# sphere_robo.net
KiCad netlist of a schematic drawn in EAGLE
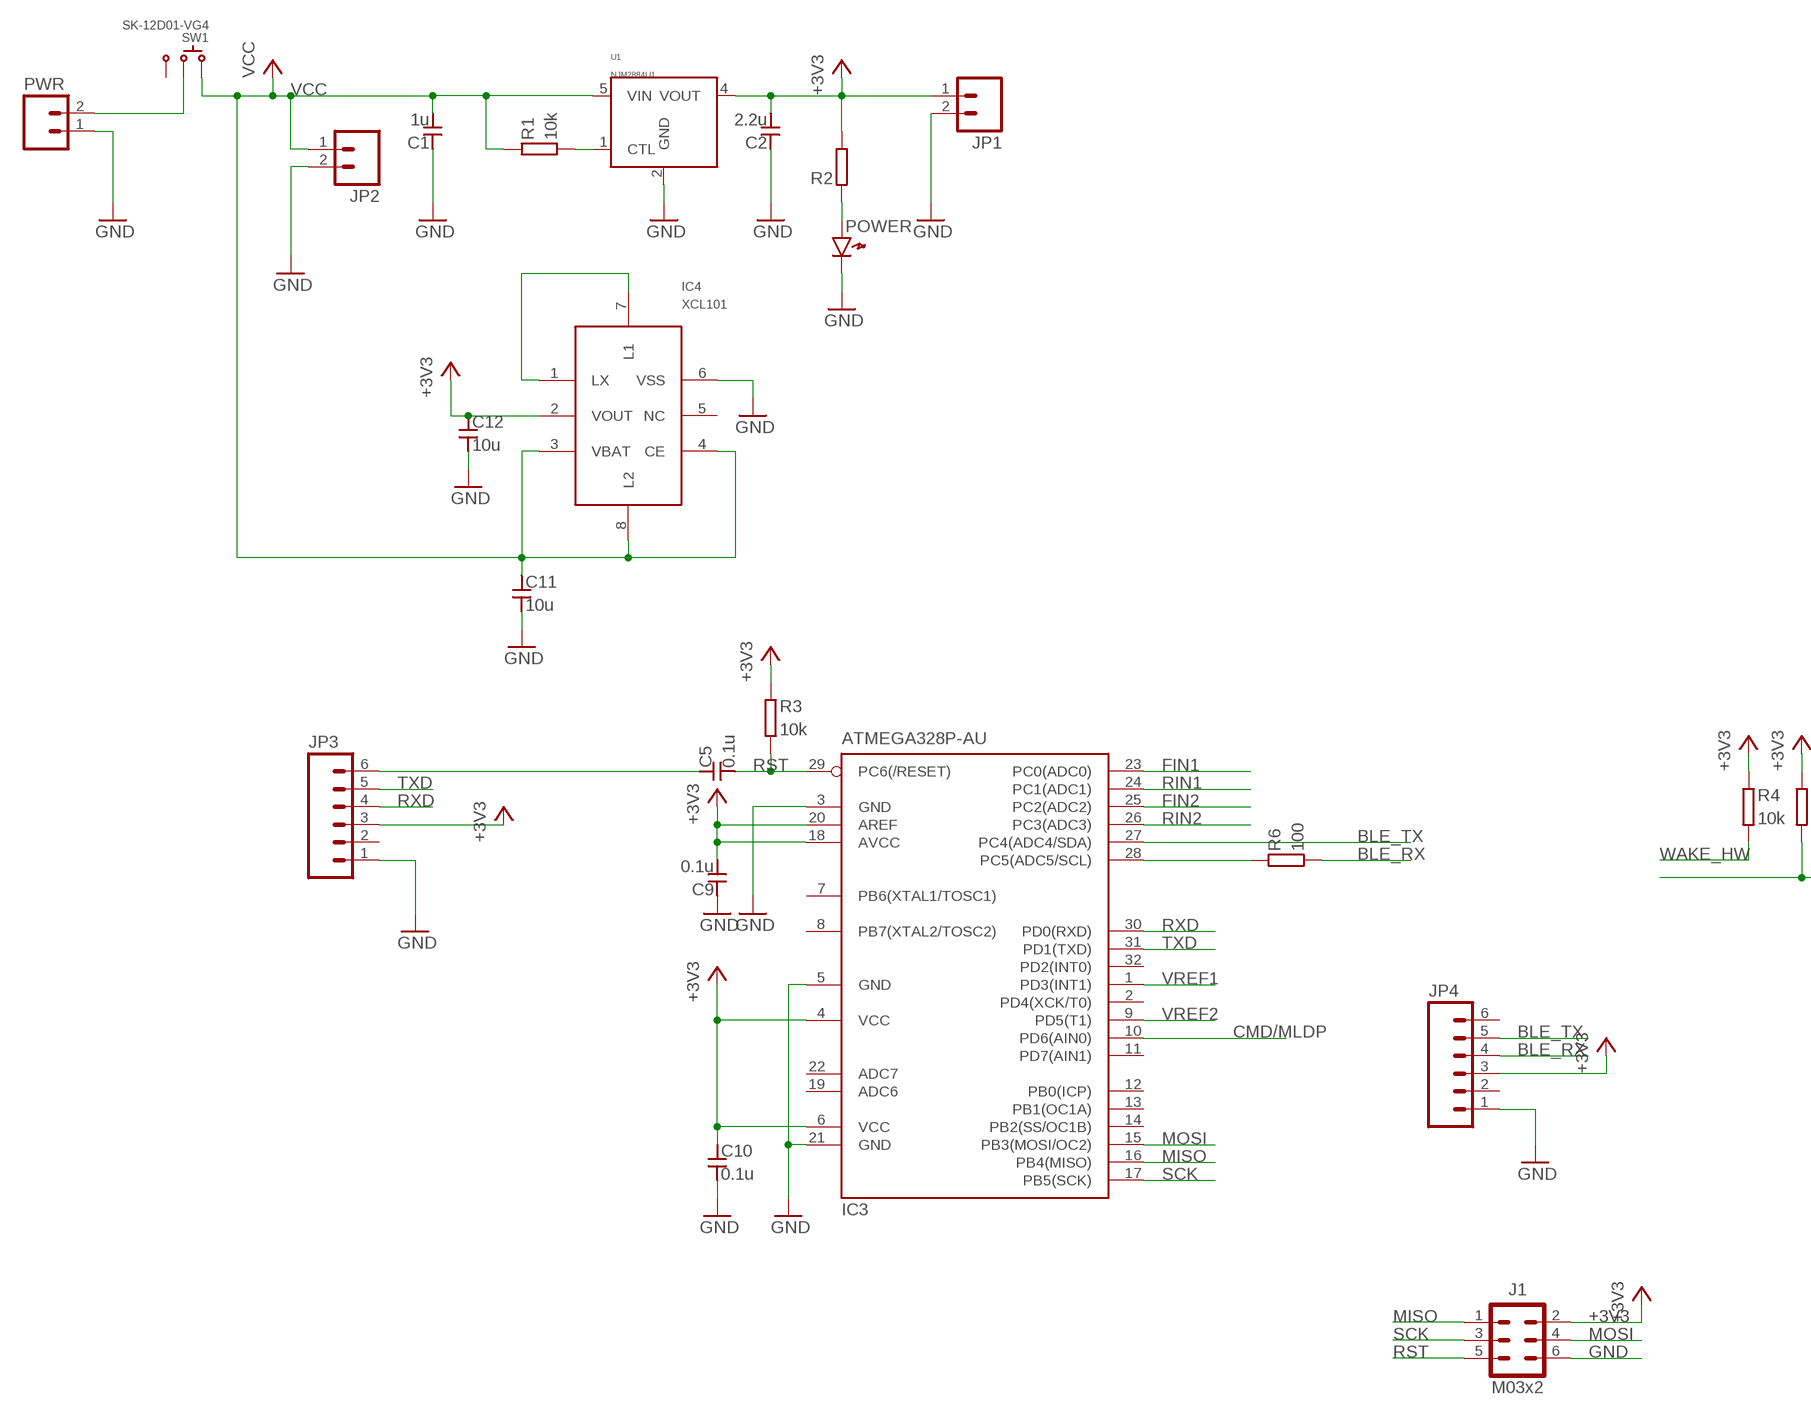
[diagram p0: schematic, sheet 1, part 1 of 2]
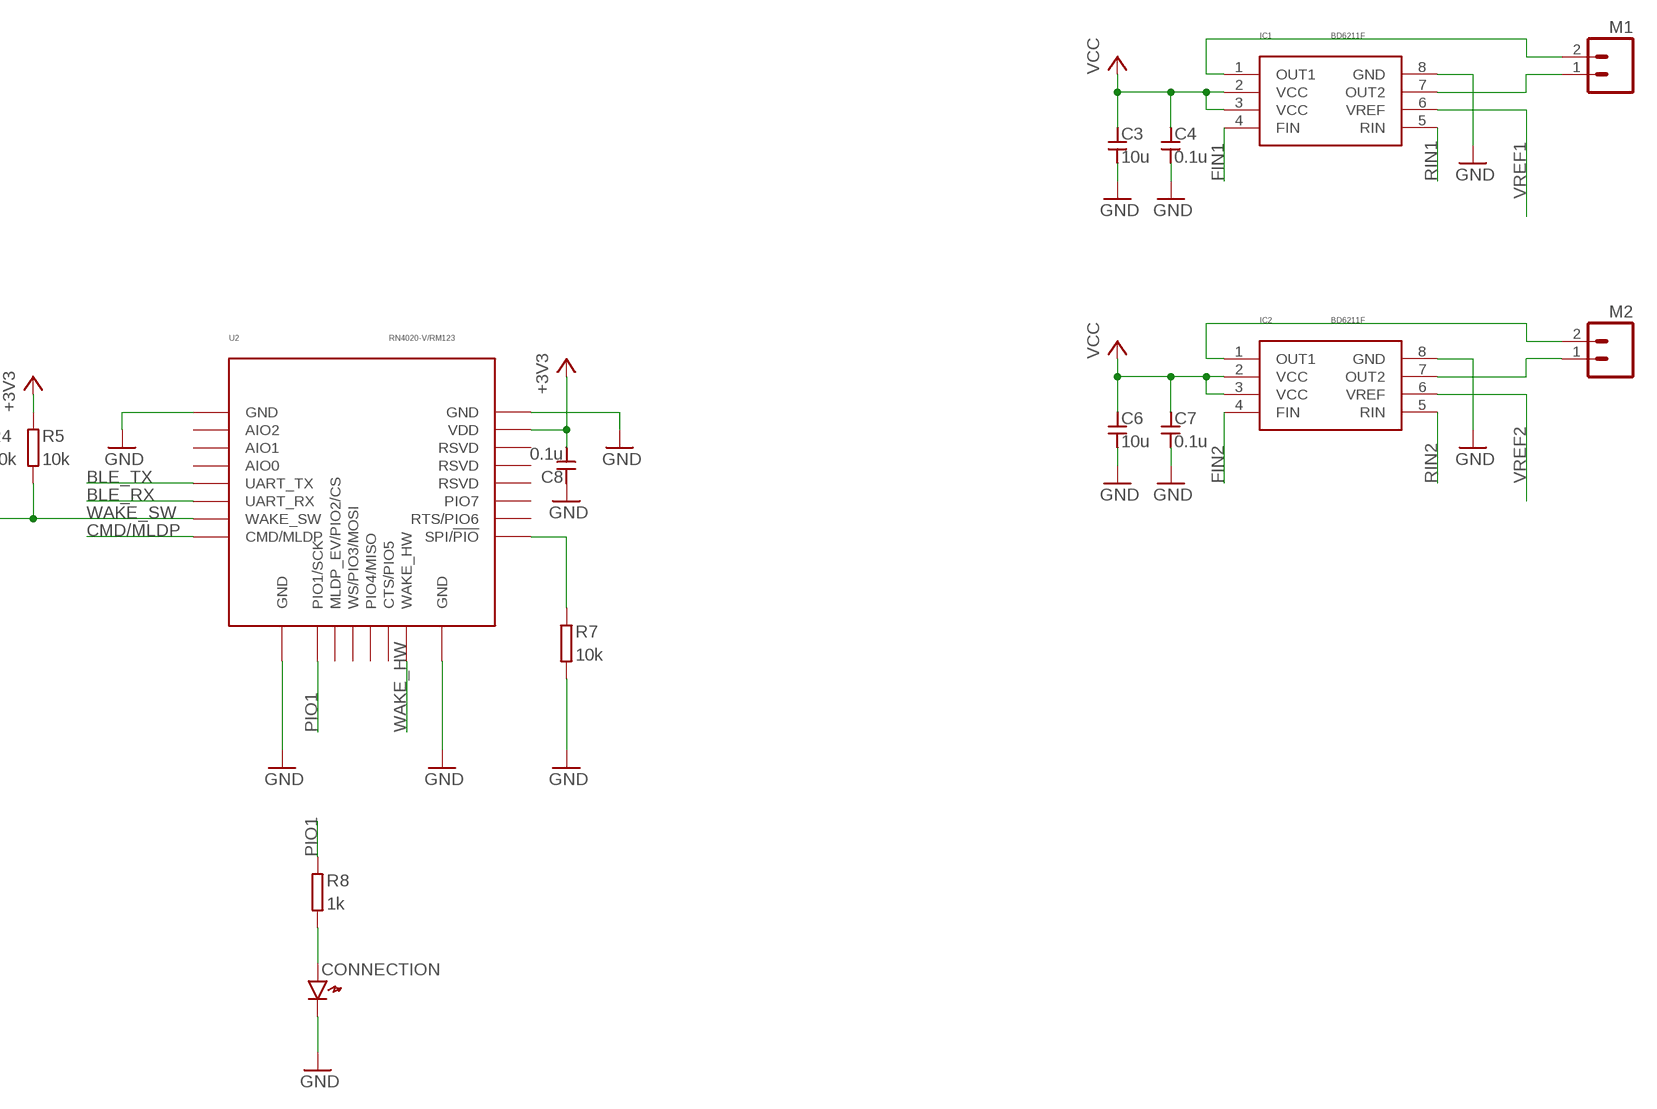
[diagram p1: schematic, sheet 1, part 2 of 2]

(export (version "E")
  (design (tool "Eeschema 10.0.6"))
  (components
    (comp (ref "C1")
      (value "1u")
      (footprint "eagle-import:SMD1608_REDUCED")
      (libsource (lib "eagle-import") (part "CAPACITOR1608_REDUCED"))
    )
    (comp (ref "C2")
      (value "2.2u")
      (footprint "eagle-import:SMD1608_REDUCED")
      (libsource (lib "eagle-import") (part "CAPACITOR1608_REDUCED"))
    )
    (comp (ref "C3")
      (value "10u")
      (footprint "eagle-import:SMD2012_REDUCED")
      (libsource (lib "eagle-import") (part "CAPACITOR2012_REDUCED"))
    )
    (comp (ref "C4")
      (value "0.1u")
      (footprint "eagle-import:SMD1608_REDUCED")
      (libsource (lib "eagle-import") (part "CAPACITOR1608_REDUCED"))
    )
    (comp (ref "C5")
      (value "0.1u")
      (footprint "eagle-import:SMD1608_REDUCED")
      (libsource (lib "eagle-import") (part "CAPACITOR1608_REDUCED"))
    )
    (comp (ref "C6")
      (value "10u")
      (footprint "eagle-import:SMD2012_REDUCED")
      (libsource (lib "eagle-import") (part "CAPACITOR2012_REDUCED"))
    )
    (comp (ref "C7")
      (value "0.1u")
      (footprint "eagle-import:SMD1608_REDUCED")
      (libsource (lib "eagle-import") (part "CAPACITOR1608_REDUCED"))
    )
    (comp (ref "C8")
      (value "0.1u")
      (footprint "eagle-import:SMD1608_REDUCED")
      (libsource (lib "eagle-import") (part "CAPACITOR1608_REDUCED"))
    )
    (comp (ref "C9")
      (value "0.1u")
      (footprint "eagle-import:SMD1608_REDUCED")
      (libsource (lib "eagle-import") (part "CAPACITOR1608_REDUCED"))
    )
    (comp (ref "C10")
      (value "0.1u")
      (footprint "eagle-import:SMD1608_REDUCED")
      (libsource (lib "eagle-import") (part "CAPACITOR1608_REDUCED"))
    )
    (comp (ref "C11")
      (value "10u")
      (footprint "eagle-import:SMD2012_REDUCED")
      (libsource (lib "eagle-import") (part "CAPACITOR2012_REDUCED"))
    )
    (comp (ref "C12")
      (value "10u")
      (footprint "eagle-import:SMD2012_REDUCED")
      (libsource (lib "eagle-import") (part "CAPACITOR2012_REDUCED"))
    )
    (comp (ref "CONNECTION")
      (value "LED1608_REDUCED")
      (footprint "eagle-import:LED1608_REDUCED")
      (libsource (lib "eagle-import") (part "LED1608_REDUCED"))
    )
    (comp (ref "IC1")
      (value "BD6211F")
      (footprint "eagle-import:SOP-8")
      (libsource (lib "eagle-import") (part "BD6211F"))
    )
    (comp (ref "IC2")
      (value "BD6211F")
      (footprint "eagle-import:SOP-8")
      (libsource (lib "eagle-import") (part "BD6211F"))
    )
    (comp (ref "IC3")
      (value "ATMEGA328P-AU")
      (footprint "eagle-import:TQFP32-08")
      (libsource (lib "eagle-import") (part "ATMEGA328P-AU"))
    )
    (comp (ref "IC4")
      (value "XCL101")
      (footprint "eagle-import:CL-2025")
      (libsource (lib "eagle-import") (part "XCL101"))
    )
    (comp (ref "J1")
      (value "M03X2STD")
      (footprint "eagle-import:2X03")
      (libsource (lib "eagle-import") (part "M03X2STD"))
    )
    (comp (ref "JP1")
      (value "M02NOSILK")
      (footprint "eagle-import:1X02-NOSILK")
      (libsource (lib "eagle-import") (part "M02NOSILK"))
    )
    (comp (ref "JP2")
      (value "M02NOSILK")
      (footprint "eagle-import:1X02-NOSILK")
      (libsource (lib "eagle-import") (part "M02NOSILK"))
    )
    (comp (ref "JP3")
      (value "M06NOSILK")
      (footprint "eagle-import:1X06-NOSILK")
      (libsource (lib "eagle-import") (part "M06NOSILK"))
    )
    (comp (ref "JP4")
      (value "M06NOSILK")
      (footprint "eagle-import:1X06-NOSILK")
      (libsource (lib "eagle-import") (part "M06NOSILK"))
    )
    (comp (ref "M1")
      (value "M02NOSILK")
      (footprint "eagle-import:1X02-NOSILK")
      (libsource (lib "eagle-import") (part "M02NOSILK"))
    )
    (comp (ref "M2")
      (value "M02NOSILK")
      (footprint "eagle-import:1X02-NOSILK")
      (libsource (lib "eagle-import") (part "M02NOSILK"))
    )
    (comp (ref "POWER")
      (value "LED1608_REDUCED")
      (footprint "eagle-import:LED1608_REDUCED")
      (libsource (lib "eagle-import") (part "LED1608_REDUCED"))
    )
    (comp (ref "PWR")
      (value "M02NOSILK")
      (footprint "eagle-import:1X02-NOSILK")
      (libsource (lib "eagle-import") (part "M02NOSILK"))
    )
    (comp (ref "R1")
      (value "10k")
      (footprint "eagle-import:SMD1608_REDUCED")
      (libsource (lib "eagle-import") (part "RESISTOR1608_REDUCED"))
    )
    (comp (ref "R2")
      (value "RESISTOR1608_REDUCED")
      (footprint "eagle-import:SMD1608_REDUCED")
      (libsource (lib "eagle-import") (part "RESISTOR1608_REDUCED"))
    )
    (comp (ref "R3")
      (value "10k")
      (footprint "eagle-import:SMD1608_REDUCED")
      (libsource (lib "eagle-import") (part "RESISTOR1608_REDUCED"))
    )
    (comp (ref "R4")
      (value "10k")
      (footprint "eagle-import:SMD1608_REDUCED")
      (libsource (lib "eagle-import") (part "RESISTOR1608_REDUCED"))
    )
    (comp (ref "R5")
      (value "10k")
      (footprint "eagle-import:SMD1608_REDUCED")
      (libsource (lib "eagle-import") (part "RESISTOR1608_REDUCED"))
    )
    (comp (ref "R6")
      (value "100")
      (footprint "eagle-import:SMD1608_REDUCED")
      (libsource (lib "eagle-import") (part "RESISTOR1608_REDUCED"))
    )
    (comp (ref "R7")
      (value "10k")
      (footprint "eagle-import:SMD1608_REDUCED")
      (libsource (lib "eagle-import") (part "RESISTOR1608_REDUCED"))
    )
    (comp (ref "R8")
      (value "1k")
      (footprint "eagle-import:SMD1608_REDUCED")
      (libsource (lib "eagle-import") (part "RESISTOR1608_REDUCED"))
    )
    (comp (ref "SW1")
      (value "SK-12D01-VG4")
      (footprint "eagle-import:SK-12D01-VG4")
      (libsource (lib "eagle-import") (part "SK-12D01-VG4"))
    )
    (comp (ref "U1")
      (value "NJM2884U1")
      (footprint "eagle-import:SOT-89-5")
      (libsource (lib "eagle-import") (part "NJM2884U1"))
    )
    (comp (ref "U2")
      (value "RN4020-V/RM123")
      (footprint "eagle-import:RN4020")
      (libsource (lib "eagle-import") (part "RN4020-V/RM123"))
    )
  )
  (nets
    (net (code "1") (name "+3V3") (class "Default")
      (node (ref "C10") (pin "1") (pinfunction "1_1") (pintype "passive"))
      (node (ref "C12") (pin "1") (pinfunction "1_1") (pintype "passive"))
      (node (ref "C2") (pin "2") (pinfunction "2_2") (pintype "passive"))
      (node (ref "C8") (pin "2") (pinfunction "2_2") (pintype "passive"))
      (node (ref "C9") (pin "2") (pinfunction "2_2") (pintype "passive"))
      (node (ref "IC3") (pin "18") (pinfunction "AVCC_18") (pintype "power_in"))
      (node (ref "IC3") (pin "20") (pinfunction "AREF_20") (pintype "passive"))
      (node (ref "IC3") (pin "4") (pinfunction "VCC_4") (pintype "power_in"))
      (node (ref "IC3") (pin "6") (pinfunction "VCC_6") (pintype "power_in"))
      (node (ref "IC4") (pin "2") (pinfunction "VOUT_2") (pintype "bidirectional"))
      (node (ref "J1") (pin "2") (pinfunction "2_2") (pintype "bidirectional"))
      (node (ref "JP1") (pin "1") (pinfunction "1_1") (pintype "passive"))
      (node (ref "JP3") (pin "3") (pinfunction "3_3") (pintype "passive"))
      (node (ref "JP4") (pin "3") (pinfunction "3_3") (pintype "passive"))
      (node (ref "R2") (pin "2") (pinfunction "2_2") (pintype "passive"))
      (node (ref "R3") (pin "1") (pinfunction "1_1") (pintype "passive"))
      (node (ref "R4") (pin "1") (pinfunction "1_1") (pintype "passive"))
      (node (ref "R5") (pin "1") (pinfunction "1_1") (pintype "passive"))
      (node (ref "U1") (pin "4") (pinfunction "VOUT_4") (pintype "bidirectional"))
      (node (ref "U2") (pin "23") (pinfunction "VDD_23") (pintype "bidirectional"))
    )
    (net (code "2") (name "/BLE_RX") (class "Default")
      (node (ref "JP4") (pin "4") (pinfunction "4_4") (pintype "passive"))
      (node (ref "R6") (pin "2") (pinfunction "2_2") (pintype "passive"))
      (node (ref "U2") (pin "6") (pinfunction "UART_RX_6") (pintype "bidirectional"))
    )
    (net (code "3") (name "/BLE_TX") (class "Default")
      (node (ref "IC3") (pin "27") (pinfunction "PC4(ADC4/SDA)_27") (pintype "bidirectional"))
      (node (ref "JP4") (pin "5") (pinfunction "5_5") (pintype "passive"))
      (node (ref "U2") (pin "5") (pinfunction "UART_TX_5") (pintype "bidirectional"))
    )
    (net (code "4") (name "/CMD{slash}MLDP") (class "Default")
      (node (ref "IC3") (pin "10") (pinfunction "PD6(AIN0)_10") (pintype "bidirectional"))
      (node (ref "U2") (pin "8") (pinfunction "CMD/MLDP_8") (pintype "bidirectional"))
    )
    (net (code "5") (name "/FIN1") (class "Default")
      (node (ref "IC1") (pin "4") (pinfunction "FIN_4") (pintype "bidirectional"))
      (node (ref "IC3") (pin "23") (pinfunction "PC0(ADC0)_23") (pintype "bidirectional"))
    )
    (net (code "6") (name "/FIN2") (class "Default")
      (node (ref "IC2") (pin "4") (pinfunction "FIN_4") (pintype "bidirectional"))
      (node (ref "IC3") (pin "25") (pinfunction "PC2(ADC2)_25") (pintype "bidirectional"))
    )
    (net (code "7") (name "/MISO") (class "Default")
      (node (ref "IC3") (pin "16") (pinfunction "PB4(MISO)_16") (pintype "bidirectional"))
      (node (ref "J1") (pin "1") (pinfunction "1_1") (pintype "bidirectional"))
    )
    (net (code "8") (name "/MOSI") (class "Default")
      (node (ref "IC3") (pin "15") (pinfunction "PB3(MOSI/OC2)_15") (pintype "bidirectional"))
      (node (ref "J1") (pin "4") (pinfunction "4_4") (pintype "bidirectional"))
    )
    (net (code "9") (name "/PIO1") (class "Default")
      (node (ref "R8") (pin "1") (pinfunction "1_1") (pintype "passive"))
      (node (ref "U2") (pin "10") (pinfunction "PIO1/SCK_10") (pintype "bidirectional"))
    )
    (net (code "10") (name "/RIN1") (class "Default")
      (node (ref "IC1") (pin "5") (pinfunction "RIN_5") (pintype "bidirectional"))
      (node (ref "IC3") (pin "24") (pinfunction "PC1(ADC1)_24") (pintype "bidirectional"))
    )
    (net (code "11") (name "/RIN2") (class "Default")
      (node (ref "IC2") (pin "5") (pinfunction "RIN_5") (pintype "bidirectional"))
      (node (ref "IC3") (pin "26") (pinfunction "PC3(ADC3)_26") (pintype "bidirectional"))
    )
    (net (code "12") (name "/RST") (class "Default")
      (node (ref "C5") (pin "2") (pinfunction "2_2") (pintype "passive"))
      (node (ref "IC3") (pin "29") (pinfunction "PC6(/RESET)_29") (pintype "bidirectional"))
      (node (ref "J1") (pin "5") (pinfunction "5_5") (pintype "bidirectional"))
      (node (ref "R3") (pin "2") (pinfunction "2_2") (pintype "passive"))
    )
    (net (code "13") (name "/RXD") (class "Default")
      (node (ref "IC3") (pin "30") (pinfunction "PD0(RXD)_30") (pintype "bidirectional"))
      (node (ref "JP3") (pin "4") (pinfunction "4_4") (pintype "passive"))
    )
    (net (code "14") (name "/SCK") (class "Default")
      (node (ref "IC3") (pin "17") (pinfunction "PB5(SCK)_17") (pintype "bidirectional"))
      (node (ref "J1") (pin "3") (pinfunction "3_3") (pintype "bidirectional"))
    )
    (net (code "15") (name "/TXD") (class "Default")
      (node (ref "IC3") (pin "31") (pinfunction "PD1(TXD)_31") (pintype "bidirectional"))
      (node (ref "JP3") (pin "5") (pinfunction "5_5") (pintype "passive"))
    )
    (net (code "16") (name "/VREF1") (class "Default")
      (node (ref "IC1") (pin "6") (pinfunction "VREF_6") (pintype "bidirectional"))
      (node (ref "IC3") (pin "1") (pinfunction "PD3(INT1)_1") (pintype "bidirectional"))
    )
    (net (code "17") (name "/VREF2") (class "Default")
      (node (ref "IC2") (pin "6") (pinfunction "VREF_6") (pintype "bidirectional"))
      (node (ref "IC3") (pin "9") (pinfunction "PD5(T1)_9") (pintype "bidirectional"))
    )
    (net (code "18") (name "/WAKE_HW") (class "Default")
      (node (ref "R4") (pin "2") (pinfunction "2_2") (pintype "passive"))
      (node (ref "U2") (pin "15") (pinfunction "WAKE_HW_15") (pintype "bidirectional"))
    )
    (net (code "19") (name "/WAKE_SW") (class "Default")
      (node (ref "R5") (pin "2") (pinfunction "2_2") (pintype "passive"))
      (node (ref "U2") (pin "7") (pinfunction "WAKE_SW_7") (pintype "bidirectional"))
    )
    (net (code "20") (name "GND") (class "Default")
      (node (ref "C1") (pin "1") (pinfunction "1_1") (pintype "passive"))
      (node (ref "C10") (pin "2") (pinfunction "2_2") (pintype "passive"))
      (node (ref "C11") (pin "2") (pinfunction "2_2") (pintype "passive"))
      (node (ref "C12") (pin "2") (pinfunction "2_2") (pintype "passive"))
      (node (ref "C2") (pin "1") (pinfunction "1_1") (pintype "passive"))
      (node (ref "C3") (pin "2") (pinfunction "2_2") (pintype "passive"))
      (node (ref "C4") (pin "2") (pinfunction "2_2") (pintype "passive"))
      (node (ref "C6") (pin "2") (pinfunction "2_2") (pintype "passive"))
      (node (ref "C7") (pin "2") (pinfunction "2_2") (pintype "passive"))
      (node (ref "C8") (pin "1") (pinfunction "1_1") (pintype "passive"))
      (node (ref "C9") (pin "1") (pinfunction "1_1") (pintype "passive"))
      (node (ref "CONNECTION") (pin "K") (pinfunction "K_K") (pintype "passive"))
      (node (ref "IC1") (pin "8") (pinfunction "GND_8") (pintype "bidirectional"))
      (node (ref "IC2") (pin "8") (pinfunction "GND_8") (pintype "bidirectional"))
      (node (ref "IC3") (pin "21") (pinfunction "GND_21") (pintype "power_in"))
      (node (ref "IC3") (pin "3") (pinfunction "GND_3") (pintype "power_in"))
      (node (ref "IC3") (pin "5") (pinfunction "GND_5") (pintype "power_in"))
      (node (ref "IC4") (pin "6") (pinfunction "VSS_6") (pintype "bidirectional"))
      (node (ref "J1") (pin "6") (pinfunction "6_6") (pintype "bidirectional"))
      (node (ref "JP1") (pin "2") (pinfunction "2_2") (pintype "passive"))
      (node (ref "JP2") (pin "2") (pinfunction "2_2") (pintype "passive"))
      (node (ref "JP3") (pin "1") (pinfunction "1_1") (pintype "passive"))
      (node (ref "JP4") (pin "1") (pinfunction "1_1") (pintype "passive"))
      (node (ref "POWER") (pin "K") (pinfunction "K_K") (pintype "passive"))
      (node (ref "PWR") (pin "1") (pinfunction "1_1") (pintype "passive"))
      (node (ref "R7") (pin "2") (pinfunction "2_2") (pintype "passive"))
      (node (ref "U1") (pin "2") (pinfunction "GND_2") (pintype "bidirectional"))
      (node (ref "U2") (pin "1") (pinfunction "GND_1") (pintype "bidirectional"))
      (node (ref "U2") (pin "16") (pinfunction "GND_16") (pintype "bidirectional"))
      (node (ref "U2") (pin "24") (pinfunction "GND_24") (pintype "bidirectional"))
      (node (ref "U2") (pin "9") (pinfunction "GND_9") (pintype "bidirectional"))
    )
    (net (code "21") (name "Net-(C5-Pad1)") (class "Default")
      (node (ref "C5") (pin "1") (pinfunction "1_1") (pintype "passive"))
      (node (ref "JP3") (pin "6") (pinfunction "6_6") (pintype "passive"))
    )
    (net (code "22") (name "Net-(CONNECTION-PadA)") (class "Default")
      (node (ref "CONNECTION") (pin "A") (pinfunction "A_A") (pintype "passive"))
      (node (ref "R8") (pin "2") (pinfunction "2_2") (pintype "passive"))
    )
    (net (code "23") (name "Net-(IC1-OUT1)") (class "Default")
      (node (ref "IC1") (pin "1") (pinfunction "OUT1_1") (pintype "bidirectional"))
      (node (ref "M1") (pin "2") (pinfunction "2_2") (pintype "passive"))
    )
    (net (code "24") (name "Net-(IC1-OUT2)") (class "Default")
      (node (ref "IC1") (pin "7") (pinfunction "OUT2_7") (pintype "bidirectional"))
      (node (ref "M1") (pin "1") (pinfunction "1_1") (pintype "passive"))
    )
    (net (code "25") (name "Net-(IC2-OUT1)") (class "Default")
      (node (ref "IC2") (pin "1") (pinfunction "OUT1_1") (pintype "bidirectional"))
      (node (ref "M2") (pin "2") (pinfunction "2_2") (pintype "passive"))
    )
    (net (code "26") (name "Net-(IC2-OUT2)") (class "Default")
      (node (ref "IC2") (pin "7") (pinfunction "OUT2_7") (pintype "bidirectional"))
      (node (ref "M2") (pin "1") (pinfunction "1_1") (pintype "passive"))
    )
    (net (code "27") (name "Net-(IC3-PC5(ADC5{slash}SCL))") (class "Default")
      (node (ref "IC3") (pin "28") (pinfunction "PC5(ADC5/SCL)_28") (pintype "bidirectional"))
      (node (ref "R6") (pin "1") (pinfunction "1_1") (pintype "passive"))
    )
    (net (code "28") (name "Net-(IC4-L1)") (class "Default")
      (node (ref "IC4") (pin "1") (pinfunction "LX_1") (pintype "bidirectional"))
      (node (ref "IC4") (pin "7") (pinfunction "L1_7") (pintype "bidirectional"))
    )
    (net (code "29") (name "Net-(POWER-PadA)") (class "Default")
      (node (ref "POWER") (pin "A") (pinfunction "A_A") (pintype "passive"))
      (node (ref "R2") (pin "1") (pinfunction "1_1") (pintype "passive"))
    )
    (net (code "30") (name "Net-(SW1-P$2)") (class "Default")
      (node (ref "PWR") (pin "2") (pinfunction "2_2") (pintype "passive"))
      (node (ref "SW1") (pin "2") (pinfunction "P$2_2") (pintype "bidirectional"))
    )
    (net (code "31") (name "Net-(U1-CTL)") (class "Default")
      (node (ref "R1") (pin "2") (pinfunction "2_2") (pintype "passive"))
      (node (ref "U1") (pin "1") (pinfunction "CTL_1") (pintype "bidirectional"))
    )
    (net (code "32") (name "Net-(U2-SPI{slash}~{PIO})") (class "Default")
      (node (ref "R7") (pin "1") (pinfunction "1_1") (pintype "passive"))
      (node (ref "U2") (pin "17") (pinfunction "SPI/~{PIO}_17") (pintype "bidirectional"))
    )
    (net (code "33") (name "VCC") (class "Default")
      (node (ref "C1") (pin "2") (pinfunction "2_2") (pintype "passive"))
      (node (ref "C11") (pin "1") (pinfunction "1_1") (pintype "passive"))
      (node (ref "C3") (pin "1") (pinfunction "1_1") (pintype "passive"))
      (node (ref "C4") (pin "1") (pinfunction "1_1") (pintype "passive"))
      (node (ref "C6") (pin "1") (pinfunction "1_1") (pintype "passive"))
      (node (ref "C7") (pin "1") (pinfunction "1_1") (pintype "passive"))
      (node (ref "IC1") (pin "2") (pinfunction "VCC_2") (pintype "bidirectional"))
      (node (ref "IC1") (pin "3") (pinfunction "VCC_3") (pintype "bidirectional"))
      (node (ref "IC2") (pin "2") (pinfunction "VCC_2") (pintype "bidirectional"))
      (node (ref "IC2") (pin "3") (pinfunction "VCC_3") (pintype "bidirectional"))
      (node (ref "IC4") (pin "3") (pinfunction "VBAT_3") (pintype "bidirectional"))
      (node (ref "IC4") (pin "4") (pinfunction "CE_4") (pintype "bidirectional"))
      (node (ref "IC4") (pin "8") (pinfunction "L2_8") (pintype "bidirectional"))
      (node (ref "JP2") (pin "1") (pinfunction "1_1") (pintype "passive"))
      (node (ref "R1") (pin "1") (pinfunction "1_1") (pintype "passive"))
      (node (ref "SW1") (pin "1") (pinfunction "P$1_1") (pintype "bidirectional"))
      (node (ref "U1") (pin "5") (pinfunction "VIN_5") (pintype "bidirectional"))
    )
    (net (code "34") (name "unconnected-(IC3-ADC6-Pad19)") (class "Default")
      (node (ref "IC3") (pin "19") (pinfunction "ADC6_19") (pintype "input"))
    )
    (net (code "35") (name "unconnected-(IC3-ADC7-Pad22)") (class "Default")
      (node (ref "IC3") (pin "22") (pinfunction "ADC7_22") (pintype "input"))
    )
    (net (code "36") (name "unconnected-(IC3-PB0(ICP)-Pad12)") (class "Default")
      (node (ref "IC3") (pin "12") (pinfunction "PB0(ICP)_12") (pintype "bidirectional"))
    )
    (net (code "37") (name "unconnected-(IC3-PB1(OC1A)-Pad13)") (class "Default")
      (node (ref "IC3") (pin "13") (pinfunction "PB1(OC1A)_13") (pintype "bidirectional"))
    )
    (net (code "38") (name "unconnected-(IC3-PB2(SS{slash}OC1B)-Pad14)") (class "Default")
      (node (ref "IC3") (pin "14") (pinfunction "PB2(SS/OC1B)_14") (pintype "bidirectional"))
    )
    (net (code "39") (name "unconnected-(IC3-PB6(XTAL1{slash}TOSC1)-Pad7)") (class "Default")
      (node (ref "IC3") (pin "7") (pinfunction "PB6(XTAL1/TOSC1)_7") (pintype "bidirectional"))
    )
    (net (code "40") (name "unconnected-(IC3-PB7(XTAL2{slash}TOSC2)-Pad8)") (class "Default")
      (node (ref "IC3") (pin "8") (pinfunction "PB7(XTAL2/TOSC2)_8") (pintype "bidirectional"))
    )
    (net (code "41") (name "unconnected-(IC3-PD2(INT0)-Pad32)") (class "Default")
      (node (ref "IC3") (pin "32") (pinfunction "PD2(INT0)_32") (pintype "bidirectional"))
    )
    (net (code "42") (name "unconnected-(IC3-PD4(XCK{slash}T0)-Pad2)") (class "Default")
      (node (ref "IC3") (pin "2") (pinfunction "PD4(XCK/T0)_2") (pintype "bidirectional"))
    )
    (net (code "43") (name "unconnected-(IC3-PD7(AIN1)-Pad11)") (class "Default")
      (node (ref "IC3") (pin "11") (pinfunction "PD7(AIN1)_11") (pintype "bidirectional"))
    )
    (net (code "44") (name "unconnected-(IC4-NC-Pad5)") (class "Default")
      (node (ref "IC4") (pin "5") (pinfunction "NC_5") (pintype "bidirectional"))
    )
    (net (code "45") (name "unconnected-(JP3-Pad2)") (class "Default")
      (node (ref "JP3") (pin "2") (pinfunction "2_2") (pintype "passive"))
    )
    (net (code "46") (name "unconnected-(JP4-Pad2)") (class "Default")
      (node (ref "JP4") (pin "2") (pinfunction "2_2") (pintype "passive"))
    )
    (net (code "47") (name "unconnected-(JP4-Pad6)") (class "Default")
      (node (ref "JP4") (pin "6") (pinfunction "6_6") (pintype "passive"))
    )
    (net (code "48") (name "unconnected-(SW1-P$3-Pad3)") (class "Default")
      (node (ref "SW1") (pin "3") (pinfunction "P$3_3") (pintype "bidirectional"))
    )
    (net (code "49") (name "unconnected-(U2-AIO0-Pad4)") (class "Default")
      (node (ref "U2") (pin "4") (pinfunction "AIO0_4") (pintype "bidirectional"))
    )
    (net (code "50") (name "unconnected-(U2-AIO1-Pad3)") (class "Default")
      (node (ref "U2") (pin "3") (pinfunction "AIO1_3") (pintype "bidirectional"))
    )
    (net (code "51") (name "unconnected-(U2-AIO2-Pad2)") (class "Default")
      (node (ref "U2") (pin "2") (pinfunction "AIO2_2") (pintype "bidirectional"))
    )
    (net (code "52") (name "unconnected-(U2-CTS{slash}PIO5-Pad14)") (class "Default")
      (node (ref "U2") (pin "14") (pinfunction "CTS/PIO5_14") (pintype "bidirectional"))
    )
    (net (code "53") (name "unconnected-(U2-MLDP_EV{slash}PIO2{slash}CS-Pad11)") (class "Default")
      (node (ref "U2") (pin "11") (pinfunction "MLDP_EV/PIO2/CS_11") (pintype "bidirectional"))
    )
    (net (code "54") (name "unconnected-(U2-PIO4{slash}MISO-Pad13)") (class "Default")
      (node (ref "U2") (pin "13") (pinfunction "PIO4/MISO_13") (pintype "bidirectional"))
    )
    (net (code "55") (name "unconnected-(U2-PIO7-Pad19)") (class "Default")
      (node (ref "U2") (pin "19") (pinfunction "PIO7_19") (pintype "bidirectional"))
    )
    (net (code "56") (name "unconnected-(U2-RSVD-Pad20)") (class "Default")
      (node (ref "U2") (pin "20") (pinfunction "RSVD_20") (pintype "bidirectional"))
    )
    (net (code "57") (name "unconnected-(U2-RSVD-Pad21)") (class "Default")
      (node (ref "U2") (pin "21") (pinfunction "RSVD_21") (pintype "bidirectional"))
    )
    (net (code "58") (name "unconnected-(U2-RSVD-Pad22)") (class "Default")
      (node (ref "U2") (pin "22") (pinfunction "RSVD_22") (pintype "bidirectional"))
    )
    (net (code "59") (name "unconnected-(U2-RTS{slash}PIO6-Pad18)") (class "Default")
      (node (ref "U2") (pin "18") (pinfunction "RTS/PIO6_18") (pintype "bidirectional"))
    )
    (net (code "60") (name "unconnected-(U2-WS{slash}PIO3{slash}MOSI-Pad12)") (class "Default")
      (node (ref "U2") (pin "12") (pinfunction "WS/PIO3/MOSI_12") (pintype "bidirectional"))
    )
  )
)
